# switch-break.net
KiCad netlist of a schematic drawn in EAGLE
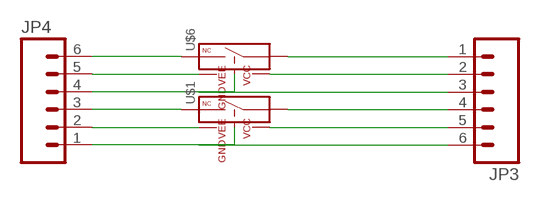
[diagram p0: schematic, sheet 1]

(export (version "E")
  (design (tool "Eeschema 10.0.6"))
  (components
    (comp (ref "JP3")
      (value "M06LONGPADS")
      (footprint "eagle-import:1X06_LONGPADS")
      (libsource (lib "eagle-import") (part "M06LONGPADS"))
    )
    (comp (ref "JP4")
      (value "M06LONGPADS")
      (footprint "eagle-import:1X06_LONGPADS")
      (libsource (lib "eagle-import") (part "M06LONGPADS"))
    )
    (comp (ref "U$1")
      (value "DG467")
      (footprint "eagle-import:TSSOP-6")
      (libsource (lib "eagle-import") (part "DG467"))
    )
    (comp (ref "U$6")
      (value "DG467")
      (footprint "eagle-import:TSSOP-6")
      (libsource (lib "eagle-import") (part "DG467"))
    )
  )
  (nets
    (net (code "1") (name "Net-(U$1A-COM)") (class "Default")
      (node (ref "JP3") (pin "4") (pinfunction "4_4") (pintype "passive"))
      (node (ref "U$1") (pin "P$6") (pinfunction "COM_P$6") (pintype "bidirectional"))
    )
    (net (code "2") (name "Net-(U$1A-CTL)") (class "Default")
      (node (ref "JP4") (pin "1") (pinfunction "1_1") (pintype "passive"))
      (node (ref "U$1") (pin "P$3") (pinfunction "CTL_P$3") (pintype "bidirectional"))
    )
    (net (code "3") (name "Net-(U$1A-IN)") (class "Default")
      (node (ref "JP4") (pin "3") (pinfunction "3_3") (pintype "passive"))
      (node (ref "U$1") (pin "P$1") (pinfunction "IN_P$1") (pintype "bidirectional"))
    )
    (net (code "4") (name "Net-(U$1B-GND)") (class "Default")
      (node (ref "JP3") (pin "6") (pinfunction "6_6") (pintype "passive"))
      (node (ref "U$1") (pin "P$4") (pinfunction "GND_P$4") (pintype "bidirectional"))
    )
    (net (code "5") (name "Net-(U$1B-VCC)") (class "Default")
      (node (ref "JP3") (pin "5") (pinfunction "5_5") (pintype "passive"))
      (node (ref "U$1") (pin "P$5") (pinfunction "VCC_P$5") (pintype "bidirectional"))
    )
    (net (code "6") (name "Net-(U$1B-VEE)") (class "Default")
      (node (ref "JP4") (pin "2") (pinfunction "2_2") (pintype "passive"))
      (node (ref "U$1") (pin "P$2") (pinfunction "VEE_P$2") (pintype "bidirectional"))
    )
    (net (code "7") (name "Net-(U$6A-COM)") (class "Default")
      (node (ref "JP3") (pin "1") (pinfunction "1_1") (pintype "passive"))
      (node (ref "U$6") (pin "P$6") (pinfunction "COM_P$6") (pintype "bidirectional"))
    )
    (net (code "8") (name "Net-(U$6A-CTL)") (class "Default")
      (node (ref "JP4") (pin "4") (pinfunction "4_4") (pintype "passive"))
      (node (ref "U$6") (pin "P$3") (pinfunction "CTL_P$3") (pintype "bidirectional"))
    )
    (net (code "9") (name "Net-(U$6A-IN)") (class "Default")
      (node (ref "JP4") (pin "6") (pinfunction "6_6") (pintype "passive"))
      (node (ref "U$6") (pin "P$1") (pinfunction "IN_P$1") (pintype "bidirectional"))
    )
    (net (code "10") (name "Net-(U$6B-GND)") (class "Default")
      (node (ref "JP3") (pin "3") (pinfunction "3_3") (pintype "passive"))
      (node (ref "U$6") (pin "P$4") (pinfunction "GND_P$4") (pintype "bidirectional"))
    )
    (net (code "11") (name "Net-(U$6B-VCC)") (class "Default")
      (node (ref "JP3") (pin "2") (pinfunction "2_2") (pintype "passive"))
      (node (ref "U$6") (pin "P$5") (pinfunction "VCC_P$5") (pintype "bidirectional"))
    )
    (net (code "12") (name "Net-(U$6B-VEE)") (class "Default")
      (node (ref "JP4") (pin "5") (pinfunction "5_5") (pintype "passive"))
      (node (ref "U$6") (pin "P$2") (pinfunction "VEE_P$2") (pintype "bidirectional"))
    )
  )
)
